# RF_RECEIVER_Schematic.net
KiCad netlist of a schematic drawn in Altium Designer
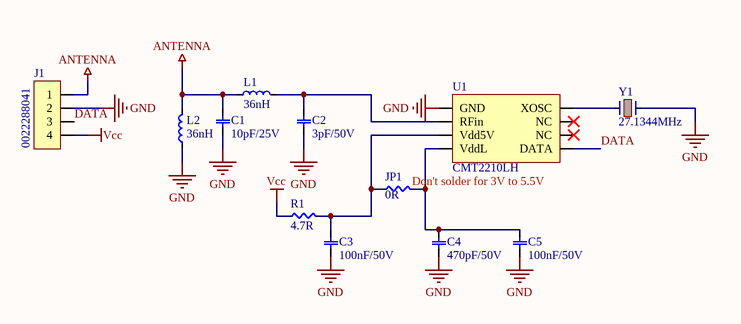
[diagram p0: RF_RECEIVER_Schematic.SchDoc]

(export (version "E")
  (design (tool "Eeschema 10.0.6"))
  (components
    (comp (ref "C1")
      (value "10pF/25V")
      (footprint "Cap_0805")
      (description "CAP CER pF 10 25V NP0 0805")
      (fields
        (field (name "MANUFACTURER") "KEMET")
        (field (name "MANUFACTURER PART NUMBER") "C0805C100J3GAC7800")
      )
      (libsource (lib "SEMATIK_LIB") (part "C0805C100J3GAC7800"))
    )
    (comp (ref "C2")
      (value "3pF/50V")
      (footprint "Cap_0805")
      (description "CAP CER pF 3 50V C0G/NPO 0805")
      (fields
        (field (name "MANUFACTURER") "Yageo")
        (field (name "MANUFACTURER PART NUMBER") "CC0805CRNPO9BN3R0")
      )
      (libsource (lib "SEMATIK_LIB") (part "CC0805CRNPO9BN3R0"))
    )
    (comp (ref "C3")
      (value "100nF/50V")
      (footprint "Cap_0805")
      (description "CAP CER nF 100 50V X7R 0805")
      (fields
        (field (name "MANUFACTURER") "TDK Corporation")
        (field (name "MANUFACTURER PART NUMBER") "C2012X7R1H104K125AE")
      )
      (libsource (lib "SEMATIK_LIB") (part "C2012X7R1H104K125AE"))
    )
    (comp (ref "C4")
      (value "470pF/50V")
      (footprint "Cap_0805")
      (description "CAP CER pF 470 50V C0G/NPO 0805")
      (fields (field (name "TOLERANCE") "5%") (field (name "VOLTAGE") "50V"))
      (libsource (lib "SEMATIK_LIB") (part "CC0805JRNPO9BN471"))
    )
    (comp (ref "C5")
      (value "100nF/50V")
      (footprint "Cap_0805")
      (description "CAP CER nF 100 50V X7R 0805")
      (fields
        (field (name "MANUFACTURER") "TDK Corporation")
        (field (name "MANUFACTURER PART NUMBER") "C2012X7R1H104K125AE")
      )
      (libsource (lib "SEMATIK_LIB") (part "C2012X7R1H104K125AE"))
    )
    (comp (ref "J1")
      (value "0022288041")
      (footprint "HDR_MALE_1x4_100mil_90DRC")
      (description "CONN HEADER 4POS R/A 2.54MM")
      (fields (field (name "MANUFACTURER") "Molex"))
      (libsource (lib "SEMATIK_LIB") (part "0022288041"))
    )
    (comp (ref "JP1")
      (value "0R")
      (footprint "R_0805")
      (description "RES SMD 0 OHM JUMPER 1/8W 0805")
      (fields
        (field (name "MANUFACTURER") "Yageo")
        (field (name "MANUFACTURER PART NUMBER") "RC0805JR-070RL")
      )
      (libsource (lib "SEMATIK_LIB") (part "RC0805JR-070RL"))
    )
    (comp (ref "L1")
      (value "36nH")
      (footprint "FERRITEBEAD_0805")
      (description "FIXED IND 36NH 500MA SMD")
      (fields
        (field (name "MANUFACTURER") "Johanson")
        (field (name "MANUFACTURER PART NUMBER") "L-15W36NGV4E")
      )
      (libsource (lib "SEMATIK_LIB") (part "L-15W36NGV4E"))
    )
    (comp (ref "L2")
      (value "36nH")
      (footprint "FERRITEBEAD_0805")
      (description "FIXED IND 36NH 500MA SMD")
      (fields
        (field (name "MANUFACTURER") "Johanson")
        (field (name "MANUFACTURER PART NUMBER") "L-15W36NGV4E")
      )
      (libsource (lib "SEMATIK_LIB") (part "L-15W36NGV4E"))
    )
    (comp (ref "R1")
      (value "4.7R")
      (footprint "R_0805")
      (description "RES SMD 4.7 OHM 5% 1/8W 0805")
      (fields
        (field (name "MANUFACTURER") "Yageo")
        (field (name "MANUFACTURER PART NUMBER") "RC0805JR-074R7L")
      )
      (libsource (lib "SEMATIK_LIB") (part "RC0805JR-074R7L"))
    )
    (comp (ref "U1")
      (value "CMT2210LH")
      (footprint "SOP8")
      (description "IC RF RX ASK/OOK 300-960MHZ 8SOIC")
      (libsource (lib "SEMATIK_LIB") (part "CMT2210LH"))
    )
    (comp (ref "Y1")
      (value "27.1344MHz")
      (footprint "CRYSTAL_SMD_DIP")
      (description "CRYSTAL 27.1344MHZ 12PF SMD")
      (fields
        (field (name "MANUFACTURER") "ECS International")
        (field (name "MANUFACTURER PART NUMBER") "ECS-271.344-CDX-0383")
      )
      (libsource (lib "SEMATIK_LIB") (part "ECS-271.344-CDX-0383"))
    )
  )
  (nets
    (net (code "1") (name "/DATA") (class "Default")
      (node (ref "J1") (pin "3") (pinfunction "3_3") (pintype "passive"))
      (node (ref "U1") (pin "5") (pinfunction "DATA_5") (pintype "passive"))
    )
    (net (code "2") (name "ANTENNA") (class "Default")
      (node (ref "C1") (pin "2") (pinfunction "2_2") (pintype "passive"))
      (node (ref "J1") (pin "1") (pinfunction "1_1") (pintype "passive"))
      (node (ref "L1") (pin "1") (pinfunction "1_1") (pintype "passive"))
      (node (ref "L2") (pin "2") (pinfunction "2_2") (pintype "passive"))
    )
    (net (code "3") (name "GND") (class "Default")
      (node (ref "C1") (pin "1") (pinfunction "1_1") (pintype "passive"))
      (node (ref "C2") (pin "1") (pinfunction "1_1") (pintype "passive"))
      (node (ref "C3") (pin "1") (pinfunction "1_1") (pintype "passive"))
      (node (ref "C4") (pin "1") (pinfunction "1_1") (pintype "passive"))
      (node (ref "C5") (pin "1") (pinfunction "1_1") (pintype "passive"))
      (node (ref "J1") (pin "2") (pinfunction "2_2") (pintype "passive"))
      (node (ref "L2") (pin "1") (pinfunction "1_1") (pintype "passive"))
      (node (ref "U1") (pin "1") (pinfunction "GND_1") (pintype "passive"))
      (node (ref "Y1") (pin "2") (pinfunction "2_2") (pintype "passive"))
    )
    (net (code "4") (name "Net-(U1-RFin)") (class "Default")
      (node (ref "C2") (pin "2") (pinfunction "2_2") (pintype "passive"))
      (node (ref "L1") (pin "2") (pinfunction "2_2") (pintype "passive"))
      (node (ref "U1") (pin "2") (pinfunction "RFin_2") (pintype "passive"))
    )
    (net (code "5") (name "Net-(U1-Vdd5V)") (class "Default")
      (node (ref "C3") (pin "2") (pinfunction "2_2") (pintype "passive"))
      (node (ref "JP1") (pin "1") (pinfunction "1_1") (pintype "passive"))
      (node (ref "R1") (pin "2") (pinfunction "2_2") (pintype "passive"))
      (node (ref "U1") (pin "3") (pinfunction "Vdd5V_3") (pintype "passive"))
    )
    (net (code "6") (name "Net-(U1-VddL)") (class "Default")
      (node (ref "C4") (pin "2") (pinfunction "2_2") (pintype "passive"))
      (node (ref "C5") (pin "2") (pinfunction "2_2") (pintype "passive"))
      (node (ref "JP1") (pin "2") (pinfunction "2_2") (pintype "passive"))
      (node (ref "U1") (pin "4") (pinfunction "VddL_4") (pintype "passive"))
    )
    (net (code "7") (name "Net-(U1-XOSC)") (class "Default")
      (node (ref "U1") (pin "8") (pinfunction "XOSC_8") (pintype "passive"))
      (node (ref "Y1") (pin "1") (pinfunction "1_1") (pintype "passive"))
    )
    (net (code "8") (name "Vcc") (class "Default")
      (node (ref "J1") (pin "4") (pinfunction "4_4") (pintype "passive"))
      (node (ref "R1") (pin "1") (pinfunction "1_1") (pintype "passive"))
    )
    (net (code "9") (name "unconnected-(U1-NC-Pad6)") (class "Default")
      (node (ref "U1") (pin "6") (pinfunction "NC_6") (pintype "passive+no_connect"))
    )
    (net (code "10") (name "unconnected-(U1-NC-Pad7)") (class "Default")
      (node (ref "U1") (pin "7") (pinfunction "NC_7") (pintype "passive+no_connect"))
    )
  )
)
